# QSPI.net
KiCad netlist of a schematic drawn in Altium Designer
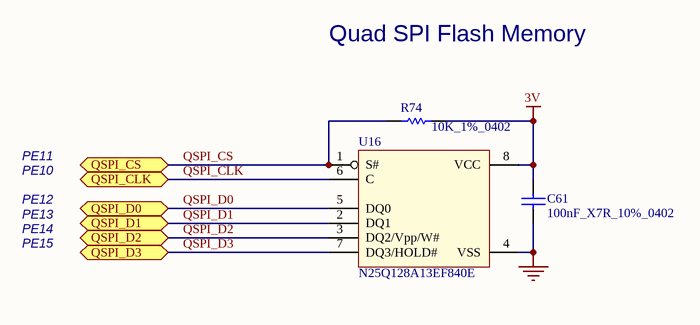
[diagram p0: QSPI.SchDoc]

(export (version "E")
  (design (tool "Eeschema 10.0.6"))
  (components
    (comp (ref "C61")
      (value "100nF_X7R_10%_0402")
      (footprint "0402C")
      (description "Capacitor,100nF,16V,X7R,10%,0402,YAGEO")
      (libsource (lib "MCD_TOOLS") (part "Cap_100nF_X7R_10%_0402"))
    )
    (comp (ref "R74")
      (value "10K_1%_0402")
      (footprint "0402R")
      (description "Resistor,10K,0402,1%,YAGEO")
      (libsource (lib "MCD_TOOLS") (part "Res_10K_1%_0402"))
    )
    (comp (ref "U16")
      (value "N25Q128A13EF840E")
      (footprint "V-PDFN-8 8x6")
      (description "128Mb, 3V, Multiple I/O Serial Flash Memory, Quad/Dual")
      (libsource (lib "MCD_TOOLS") (part "N25Q128A13EF840E"))
    )
  )
  (nets
    (net (code "1") (name "/QSPI_CLK") (class "Default")
      (node (ref "U16") (pin "6") (pinfunction "C_6") (pintype "passive"))
    )
    (net (code "2") (name "/QSPI_CS") (class "Default")
      (node (ref "R74") (pin "1") (pinfunction "1_1") (pintype "passive"))
      (node (ref "U16") (pin "1") (pinfunction "S#_1") (pintype "passive"))
    )
    (net (code "3") (name "/QSPI_D0") (class "Default")
      (node (ref "U16") (pin "5") (pinfunction "DQ0_5") (pintype "passive"))
    )
    (net (code "4") (name "/QSPI_D1") (class "Default")
      (node (ref "U16") (pin "2") (pinfunction "DQ1_2") (pintype "passive"))
    )
    (net (code "5") (name "/QSPI_D2") (class "Default")
      (node (ref "U16") (pin "3") (pinfunction "DQ2/Vpp/W#_3") (pintype "passive"))
    )
    (net (code "6") (name "/QSPI_D3") (class "Default")
      (node (ref "U16") (pin "7") (pinfunction "DQ3/HOLD#_7") (pintype "passive"))
    )
    (net (code "7") (name "3V") (class "Default")
      (node (ref "C61") (pin "2") (pinfunction "2_2") (pintype "passive"))
      (node (ref "R74") (pin "2") (pinfunction "2_2") (pintype "passive"))
      (node (ref "U16") (pin "8") (pinfunction "VCC_8") (pintype "passive"))
    )
    (net (code "8") (name "GND") (class "Default")
      (node (ref "C61") (pin "1") (pinfunction "1_1") (pintype "passive"))
      (node (ref "U16") (pin "4") (pinfunction "VSS_4") (pintype "passive"))
    )
  )
)
